# BpodMainBoard_r0_5_1.net
KiCad netlist of a schematic drawn in EAGLE
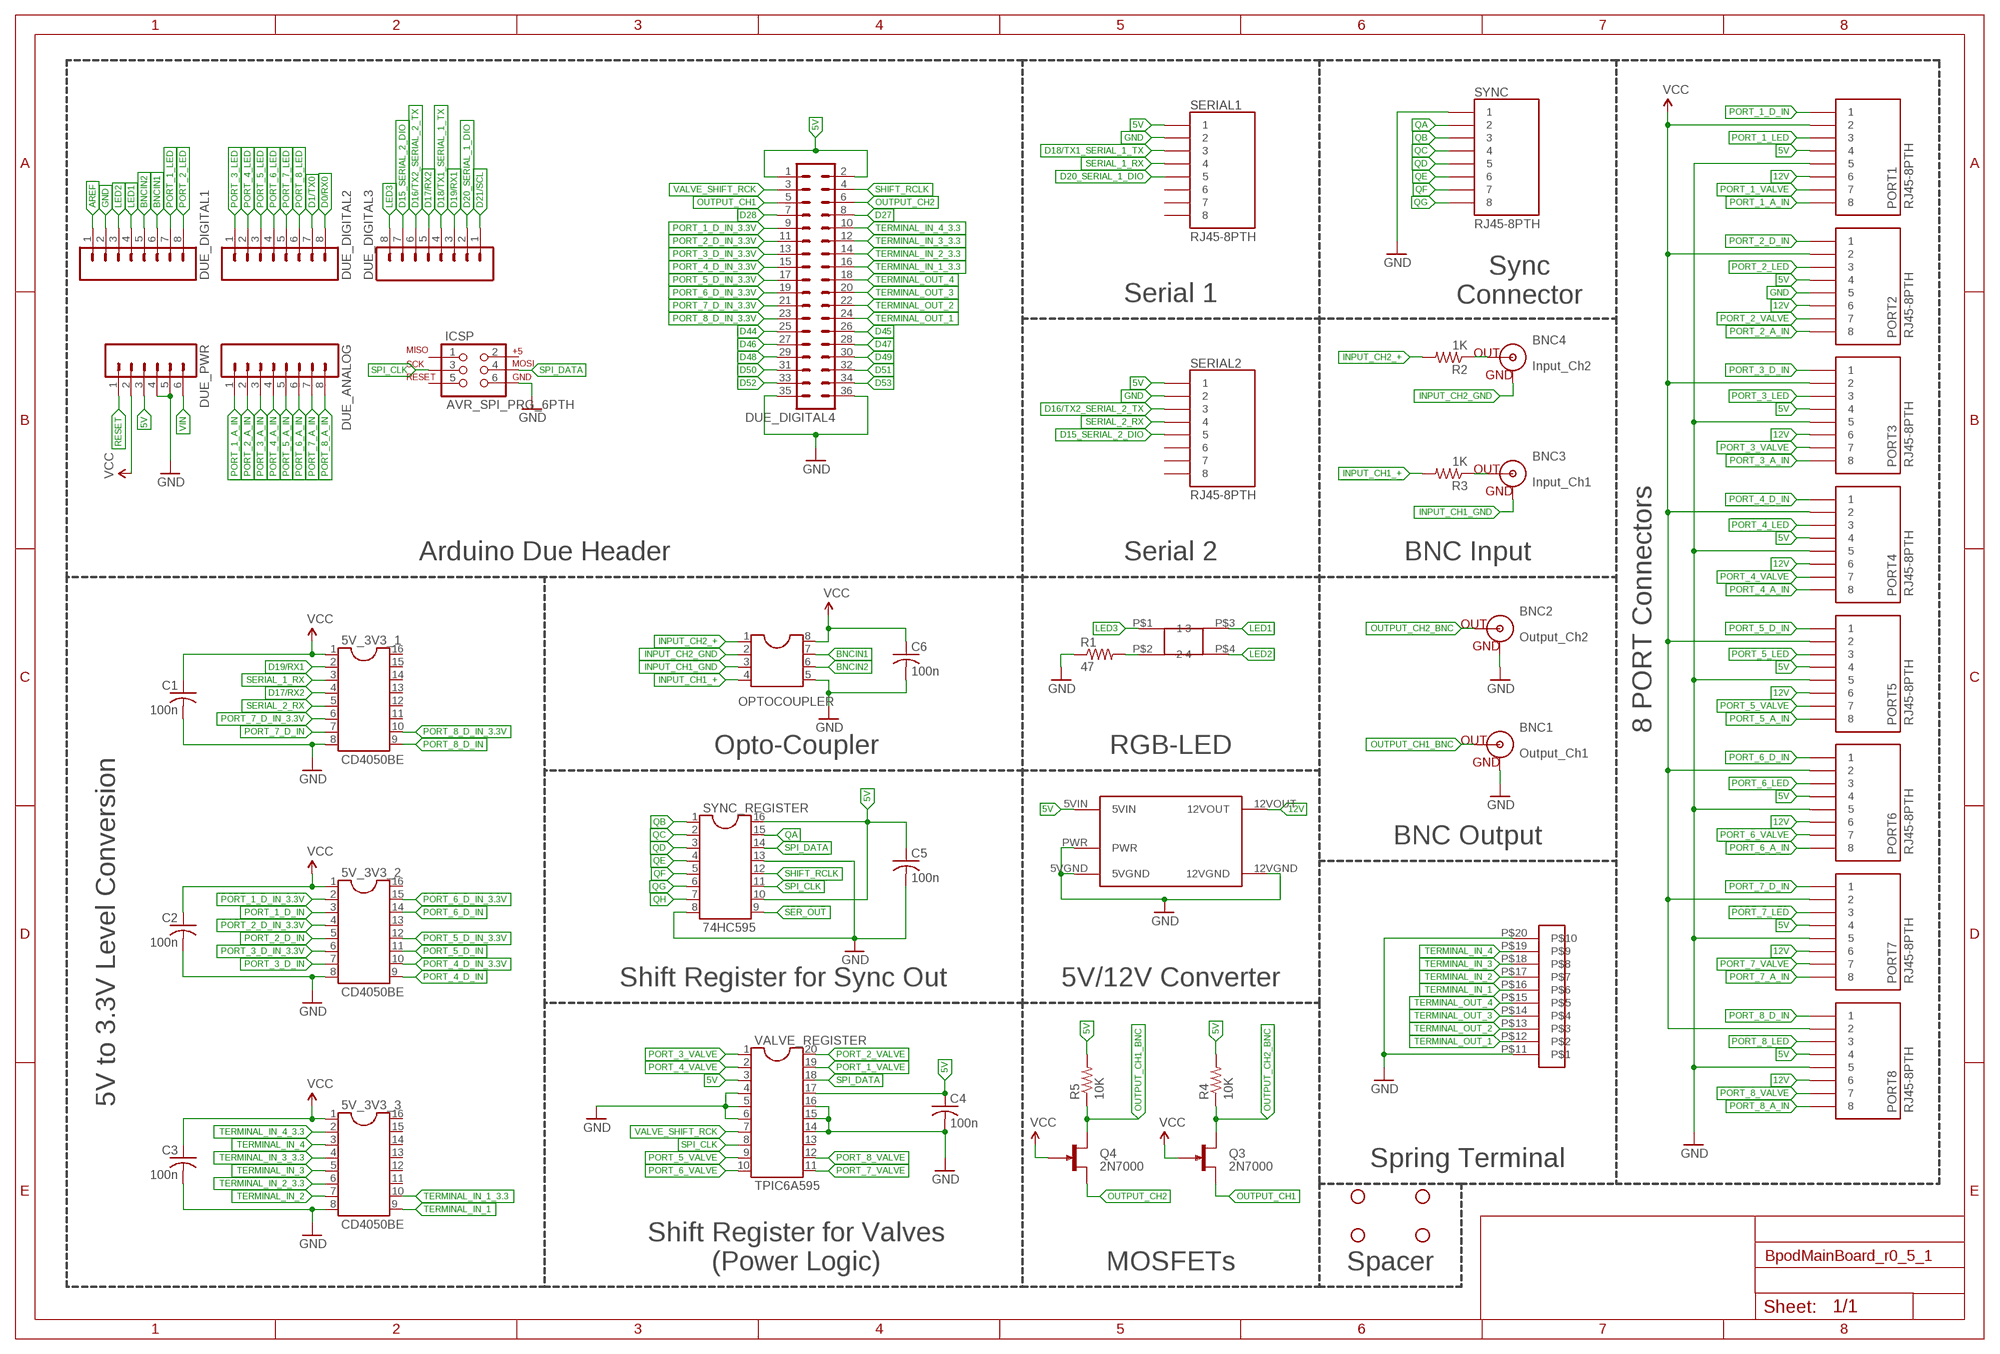
[diagram p0: schematic, sheet 1]

(export (version "E")
  (design (tool "Eeschema 10.0.6"))
  (components
    (comp (ref "5V_3V3_1")
      (value "CD4050BE")
      (footprint "eagle-import:DIL16")
      (libsource (lib "eagle-import") (part "DIL16"))
    )
    (comp (ref "5V_3V3_2")
      (value "CD4050BE")
      (footprint "eagle-import:DIL16")
      (libsource (lib "eagle-import") (part "DIL16"))
    )
    (comp (ref "5V_3V3_3")
      (value "CD4050BE")
      (footprint "eagle-import:DIL16")
      (libsource (lib "eagle-import") (part "DIL16"))
    )
    (comp (ref "BNC1")
      (value "Output_Ch1")
      (footprint "eagle-import:BNC")
      (libsource (lib "eagle-import") (part "BNCPTH"))
    )
    (comp (ref "BNC2")
      (value "Output_Ch2")
      (footprint "eagle-import:BNC")
      (libsource (lib "eagle-import") (part "BNCPTH"))
    )
    (comp (ref "BNC3")
      (value "Input_Ch1")
      (footprint "eagle-import:BNC")
      (libsource (lib "eagle-import") (part "BNCPTH"))
    )
    (comp (ref "BNC4")
      (value "Input_Ch2")
      (footprint "eagle-import:BNC")
      (libsource (lib "eagle-import") (part "BNCPTH"))
    )
    (comp (ref "C1")
      (value "100n")
      (footprint "eagle-import:C025-024X044")
      (libsource (lib "eagle-import") (part "C-US025-024X044"))
    )
    (comp (ref "C2")
      (value "100n")
      (footprint "eagle-import:C025-024X044")
      (libsource (lib "eagle-import") (part "C-US025-024X044"))
    )
    (comp (ref "C3")
      (value "100n")
      (footprint "eagle-import:C025-024X044")
      (libsource (lib "eagle-import") (part "C-US025-024X044"))
    )
    (comp (ref "C4")
      (value "100n")
      (footprint "eagle-import:C025-024X044")
      (libsource (lib "eagle-import") (part "C-US025-024X044"))
    )
    (comp (ref "C5")
      (value "100n")
      (footprint "eagle-import:C025-024X044")
      (libsource (lib "eagle-import") (part "C-US025-024X044"))
    )
    (comp (ref "C6")
      (value "100n")
      (footprint "eagle-import:C025-024X044")
      (libsource (lib "eagle-import") (part "C-US025-024X044"))
    )
    (comp (ref "DUE_ANALOG")
      (value "M081X08")
      (footprint "eagle-import:1X08")
      (libsource (lib "eagle-import") (part "M081X08"))
    )
    (comp (ref "DUE_DIGITAL1")
      (value "M081X08")
      (footprint "eagle-import:1X08")
      (libsource (lib "eagle-import") (part "M081X08"))
    )
    (comp (ref "DUE_DIGITAL2")
      (value "M081X08")
      (footprint "eagle-import:1X08")
      (libsource (lib "eagle-import") (part "M081X08"))
    )
    (comp (ref "DUE_DIGITAL3")
      (value "M081X08")
      (footprint "eagle-import:1X08")
      (libsource (lib "eagle-import") (part "M081X08"))
    )
    (comp (ref "DUE_DIGITAL4")
      (value "MA18-2")
      (footprint "eagle-import:MA18-2")
      (libsource (lib "eagle-import") (part "MA18-2"))
    )
    (comp (ref "DUE_PWR")
      (value "M06SIP")
      (footprint "eagle-import:1X06")
      (fields (field (name "SPICEPREFIX") "X"))
      (libsource (lib "eagle-import") (part "M06SIP"))
    )
    (comp (ref "ICSP")
      (value "AVR_SPI_PRG_6PTH")
      (footprint "eagle-import:2X3")
      (libsource (lib "eagle-import") (part "AVR_SPI_PRG_6PTH"))
    )
    (comp (ref "JP1")
      (value "STAND-OFF")
      (footprint "eagle-import:STAND-OFF")
      (libsource (lib "eagle-import") (part "STAND-OFF"))
    )
    (comp (ref "JP2")
      (value "STAND-OFF")
      (footprint "eagle-import:STAND-OFF")
      (libsource (lib "eagle-import") (part "STAND-OFF"))
    )
    (comp (ref "JP3")
      (value "STAND-OFF")
      (footprint "eagle-import:STAND-OFF")
      (libsource (lib "eagle-import") (part "STAND-OFF"))
    )
    (comp (ref "JP4")
      (value "STAND-OFF")
      (footprint "eagle-import:STAND-OFF")
      (libsource (lib "eagle-import") (part "STAND-OFF"))
    )
    (comp (ref "OPTOCOUPLER")
      (value "DIL8")
      (footprint "eagle-import:DIL08")
      (libsource (lib "eagle-import") (part "DIL8"))
    )
    (comp (ref "PORT1")
      (value "RJ45-8PTH")
      (footprint "eagle-import:RJ45-8")
      (libsource (lib "eagle-import") (part "RJ45-8PTH"))
    )
    (comp (ref "PORT2")
      (value "RJ45-8PTH")
      (footprint "eagle-import:RJ45-8")
      (libsource (lib "eagle-import") (part "RJ45-8PTH"))
    )
    (comp (ref "PORT3")
      (value "RJ45-8PTH")
      (footprint "eagle-import:RJ45-8")
      (libsource (lib "eagle-import") (part "RJ45-8PTH"))
    )
    (comp (ref "PORT4")
      (value "RJ45-8PTH")
      (footprint "eagle-import:RJ45-8")
      (libsource (lib "eagle-import") (part "RJ45-8PTH"))
    )
    (comp (ref "PORT5")
      (value "RJ45-8PTH")
      (footprint "eagle-import:RJ45-8")
      (libsource (lib "eagle-import") (part "RJ45-8PTH"))
    )
    (comp (ref "PORT6")
      (value "RJ45-8PTH")
      (footprint "eagle-import:RJ45-8")
      (libsource (lib "eagle-import") (part "RJ45-8PTH"))
    )
    (comp (ref "PORT7")
      (value "RJ45-8PTH")
      (footprint "eagle-import:RJ45-8")
      (libsource (lib "eagle-import") (part "RJ45-8PTH"))
    )
    (comp (ref "PORT8")
      (value "RJ45-8PTH")
      (footprint "eagle-import:RJ45-8")
      (libsource (lib "eagle-import") (part "RJ45-8PTH"))
    )
    (comp (ref "Q3")
      (value "2N7000")
      (footprint "eagle-import:TO92F")
      (libsource (lib "eagle-import") (part "2N3819"))
    )
    (comp (ref "Q4")
      (value "2N7000")
      (footprint "eagle-import:TO92F")
      (libsource (lib "eagle-import") (part "2N3819"))
    )
    (comp (ref "R1")
      (value "47")
      (footprint "eagle-import:0207_10")
      (libsource (lib "eagle-import") (part "R-US_0207/10"))
    )
    (comp (ref "R2")
      (value "1K")
      (footprint "eagle-import:0207_10")
      (libsource (lib "eagle-import") (part "R-US_0207/10"))
    )
    (comp (ref "R3")
      (value "1K")
      (footprint "eagle-import:0207_10")
      (libsource (lib "eagle-import") (part "R-US_0207/10"))
    )
    (comp (ref "R4")
      (value "10K")
      (footprint "eagle-import:0207_10")
      (libsource (lib "eagle-import") (part "R-US_0207/10"))
    )
    (comp (ref "R5")
      (value "10K")
      (footprint "eagle-import:0207_10")
      (libsource (lib "eagle-import") (part "R-US_0207/10"))
    )
    (comp (ref "SERIAL1")
      (value "RJ45-8PTH")
      (footprint "eagle-import:RJ45-8")
      (libsource (lib "eagle-import") (part "RJ45-8PTH"))
    )
    (comp (ref "SERIAL2")
      (value "RJ45-8PTH")
      (footprint "eagle-import:RJ45-8")
      (libsource (lib "eagle-import") (part "RJ45-8PTH"))
    )
    (comp (ref "SPRINGTERMINAL")
      (value "10POS_SPRING_TERMINAL")
      (footprint "eagle-import:10POS_SCREW_TERMINAL")
      (libsource (lib "eagle-import") (part "10POS_SPRING_TERMINAL"))
    )
    (comp (ref "SYNC")
      (value "RJ45-8PTH")
      (footprint "eagle-import:RJ45-8")
      (libsource (lib "eagle-import") (part "RJ45-8PTH"))
    )
    (comp (ref "SYNC_REGISTER")
      (value "74HC595")
      (footprint "eagle-import:DIL16")
      (libsource (lib "eagle-import") (part "DIL16"))
    )
    (comp (ref "U$5")
      (value "TDK_LAMBDA_5V_TO_12V")
      (footprint "eagle-import:TDK_LAMBDA_5V_12V")
      (libsource (lib "eagle-import") (part "TDK_LAMBDA_5V_TO_12V"))
    )
    (comp (ref "U$8")
      (value "SQUARE_TRICOLOR_LED")
      (footprint "eagle-import:SQUARE_TRICOLOR_LED")
      (libsource (lib "eagle-import") (part "SQUARE_TRICOLOR_LED"))
    )
    (comp (ref "VALVE_REGISTER")
      (value "TPIC6A595")
      (footprint "eagle-import:DIL20")
      (libsource (lib "eagle-import") (part "DIL20"))
    )
  )
  (nets
    (net (code "1") (name "5V") (class "Default")
      (node (ref "C4") (pin "1") (pinfunction "1_1") (pintype "passive"))
      (node (ref "C5") (pin "1") (pinfunction "1_1") (pintype "passive"))
      (node (ref "DUE_DIGITAL4") (pin "1") (pinfunction "1_1") (pintype "passive"))
      (node (ref "DUE_DIGITAL4") (pin "2") (pinfunction "2_2") (pintype "passive"))
      (node (ref "DUE_PWR") (pin "3") (pinfunction "3_3") (pintype "passive"))
      (node (ref "PORT1") (pin "4") (pinfunction "4_4") (pintype "bidirectional"))
      (node (ref "PORT2") (pin "4") (pinfunction "4_4") (pintype "bidirectional"))
      (node (ref "PORT3") (pin "4") (pinfunction "4_4") (pintype "bidirectional"))
      (node (ref "PORT4") (pin "4") (pinfunction "4_4") (pintype "bidirectional"))
      (node (ref "PORT5") (pin "4") (pinfunction "4_4") (pintype "bidirectional"))
      (node (ref "PORT6") (pin "4") (pinfunction "4_4") (pintype "bidirectional"))
      (node (ref "PORT7") (pin "4") (pinfunction "4_4") (pintype "bidirectional"))
      (node (ref "PORT8") (pin "4") (pinfunction "4_4") (pintype "bidirectional"))
      (node (ref "R4") (pin "2") (pinfunction "2_2") (pintype "passive"))
      (node (ref "R5") (pin "2") (pinfunction "2_2") (pintype "passive"))
      (node (ref "SERIAL1") (pin "1") (pinfunction "1_1") (pintype "bidirectional"))
      (node (ref "SERIAL2") (pin "1") (pinfunction "1_1") (pintype "bidirectional"))
      (node (ref "SYNC_REGISTER") (pin "10") (pinfunction "10_10") (pintype "passive"))
      (node (ref "SYNC_REGISTER") (pin "16") (pinfunction "16_16") (pintype "passive"))
      (node (ref "U$5") (pin "5VIN") (pinfunction "5VIN_5VIN") (pintype "bidirectional"))
      (node (ref "VALVE_REGISTER") (pin "17") (pinfunction "17_17") (pintype "passive"))
      (node (ref "VALVE_REGISTER") (pin "3") (pinfunction "3_3") (pintype "passive"))
    )
    (net (code "2") (name "12V") (class "Default")
      (node (ref "PORT1") (pin "6") (pinfunction "6_6") (pintype "bidirectional"))
      (node (ref "PORT2") (pin "6") (pinfunction "6_6") (pintype "bidirectional"))
      (node (ref "PORT3") (pin "6") (pinfunction "6_6") (pintype "bidirectional"))
      (node (ref "PORT4") (pin "6") (pinfunction "6_6") (pintype "bidirectional"))
      (node (ref "PORT5") (pin "6") (pinfunction "6_6") (pintype "bidirectional"))
      (node (ref "PORT6") (pin "6") (pinfunction "6_6") (pintype "bidirectional"))
      (node (ref "PORT7") (pin "6") (pinfunction "6_6") (pintype "bidirectional"))
      (node (ref "PORT8") (pin "6") (pinfunction "6_6") (pintype "bidirectional"))
      (node (ref "U$5") (pin "12VOUT") (pinfunction "12VOUT_12VOUT") (pintype "bidirectional"))
    )
    (net (code "3") (name "AREF") (class "Default")
      (node (ref "DUE_DIGITAL1") (pin "1") (pinfunction "1_1") (pintype "passive"))
    )
    (net (code "4") (name "BNCIN1") (class "Default")
      (node (ref "DUE_DIGITAL1") (pin "6") (pinfunction "6_6") (pintype "passive"))
      (node (ref "OPTOCOUPLER") (pin "7") (pinfunction "7_7") (pintype "passive"))
    )
    (net (code "5") (name "BNCIN2") (class "Default")
      (node (ref "DUE_DIGITAL1") (pin "5") (pinfunction "5_5") (pintype "passive"))
      (node (ref "OPTOCOUPLER") (pin "6") (pinfunction "6_6") (pintype "passive"))
    )
    (net (code "6") (name "D0{slash}RX0") (class "Default")
      (node (ref "DUE_DIGITAL2") (pin "8") (pinfunction "8_8") (pintype "passive"))
    )
    (net (code "7") (name "D1{slash}TX0") (class "Default")
      (node (ref "DUE_DIGITAL2") (pin "7") (pinfunction "7_7") (pintype "passive"))
    )
    (net (code "8") (name "D15_SERIAL_2_DIO") (class "Default")
      (node (ref "DUE_DIGITAL3") (pin "7") (pinfunction "7_7") (pintype "passive"))
      (node (ref "SERIAL2") (pin "5") (pinfunction "5_5") (pintype "bidirectional"))
    )
    (net (code "9") (name "D16{slash}TX2_SERIAL_2_TX") (class "Default")
      (node (ref "DUE_DIGITAL3") (pin "6") (pinfunction "6_6") (pintype "passive"))
      (node (ref "SERIAL2") (pin "3") (pinfunction "3_3") (pintype "bidirectional"))
    )
    (net (code "10") (name "D17{slash}RX2") (class "Default")
      (node (ref "5V_3V3_1") (pin "4") (pinfunction "4_4") (pintype "passive"))
      (node (ref "DUE_DIGITAL3") (pin "5") (pinfunction "5_5") (pintype "passive"))
    )
    (net (code "11") (name "D18{slash}TX1_SERIAL_1_TX") (class "Default")
      (node (ref "DUE_DIGITAL3") (pin "4") (pinfunction "4_4") (pintype "passive"))
      (node (ref "SERIAL1") (pin "3") (pinfunction "3_3") (pintype "bidirectional"))
    )
    (net (code "12") (name "D19{slash}RX1") (class "Default")
      (node (ref "5V_3V3_1") (pin "2") (pinfunction "2_2") (pintype "passive"))
      (node (ref "DUE_DIGITAL3") (pin "3") (pinfunction "3_3") (pintype "passive"))
    )
    (net (code "13") (name "D20_SERIAL_1_DIO") (class "Default")
      (node (ref "DUE_DIGITAL3") (pin "2") (pinfunction "2_2") (pintype "passive"))
      (node (ref "SERIAL1") (pin "5") (pinfunction "5_5") (pintype "bidirectional"))
    )
    (net (code "14") (name "D21{slash}SCL") (class "Default")
      (node (ref "DUE_DIGITAL3") (pin "1") (pinfunction "1_1") (pintype "passive"))
    )
    (net (code "15") (name "D27") (class "Default")
      (node (ref "DUE_DIGITAL4") (pin "8") (pinfunction "8_8") (pintype "passive"))
    )
    (net (code "16") (name "D28") (class "Default")
      (node (ref "DUE_DIGITAL4") (pin "7") (pinfunction "7_7") (pintype "passive"))
    )
    (net (code "17") (name "D44") (class "Default")
      (node (ref "DUE_DIGITAL4") (pin "25") (pinfunction "25_25") (pintype "passive"))
    )
    (net (code "18") (name "D45") (class "Default")
      (node (ref "DUE_DIGITAL4") (pin "26") (pinfunction "26_26") (pintype "passive"))
    )
    (net (code "19") (name "D46") (class "Default")
      (node (ref "DUE_DIGITAL4") (pin "27") (pinfunction "27_27") (pintype "passive"))
    )
    (net (code "20") (name "D47") (class "Default")
      (node (ref "DUE_DIGITAL4") (pin "28") (pinfunction "28_28") (pintype "passive"))
    )
    (net (code "21") (name "D48") (class "Default")
      (node (ref "DUE_DIGITAL4") (pin "29") (pinfunction "29_29") (pintype "passive"))
    )
    (net (code "22") (name "D49") (class "Default")
      (node (ref "DUE_DIGITAL4") (pin "30") (pinfunction "30_30") (pintype "passive"))
    )
    (net (code "23") (name "D50") (class "Default")
      (node (ref "DUE_DIGITAL4") (pin "31") (pinfunction "31_31") (pintype "passive"))
    )
    (net (code "24") (name "D51") (class "Default")
      (node (ref "DUE_DIGITAL4") (pin "32") (pinfunction "32_32") (pintype "passive"))
    )
    (net (code "25") (name "D52") (class "Default")
      (node (ref "DUE_DIGITAL4") (pin "33") (pinfunction "33_33") (pintype "passive"))
    )
    (net (code "26") (name "D53") (class "Default")
      (node (ref "DUE_DIGITAL4") (pin "34") (pinfunction "34_34") (pintype "passive"))
    )
    (net (code "27") (name "GND") (class "Default")
      (node (ref "5V_3V3_1") (pin "8") (pinfunction "8_8") (pintype "passive"))
      (node (ref "5V_3V3_2") (pin "8") (pinfunction "8_8") (pintype "passive"))
      (node (ref "5V_3V3_3") (pin "8") (pinfunction "8_8") (pintype "passive"))
      (node (ref "BNC1") (pin "GND") (pinfunction "GND_GND") (pintype "bidirectional"))
      (node (ref "BNC2") (pin "GND") (pinfunction "GND_GND") (pintype "bidirectional"))
      (node (ref "C1") (pin "2") (pinfunction "2_2") (pintype "passive"))
      (node (ref "C2") (pin "2") (pinfunction "2_2") (pintype "passive"))
      (node (ref "C3") (pin "2") (pinfunction "2_2") (pintype "passive"))
      (node (ref "C4") (pin "2") (pinfunction "2_2") (pintype "passive"))
      (node (ref "C5") (pin "2") (pinfunction "2_2") (pintype "passive"))
      (node (ref "C6") (pin "2") (pinfunction "2_2") (pintype "passive"))
      (node (ref "DUE_DIGITAL1") (pin "2") (pinfunction "2_2") (pintype "passive"))
      (node (ref "DUE_DIGITAL4") (pin "35") (pinfunction "35_35") (pintype "passive"))
      (node (ref "DUE_DIGITAL4") (pin "36") (pinfunction "36_36") (pintype "passive"))
      (node (ref "DUE_PWR") (pin "4") (pinfunction "4_4") (pintype "passive"))
      (node (ref "DUE_PWR") (pin "5") (pinfunction "5_5") (pintype "passive"))
      (node (ref "ICSP") (pin "6") (pinfunction "6_6") (pintype "passive"))
      (node (ref "OPTOCOUPLER") (pin "5") (pinfunction "5_5") (pintype "passive"))
      (node (ref "PORT1") (pin "5") (pinfunction "5_5") (pintype "bidirectional"))
      (node (ref "PORT2") (pin "5") (pinfunction "5_5") (pintype "bidirectional"))
      (node (ref "PORT3") (pin "5") (pinfunction "5_5") (pintype "bidirectional"))
      (node (ref "PORT4") (pin "5") (pinfunction "5_5") (pintype "bidirectional"))
      (node (ref "PORT5") (pin "5") (pinfunction "5_5") (pintype "bidirectional"))
      (node (ref "PORT6") (pin "5") (pinfunction "5_5") (pintype "bidirectional"))
      (node (ref "PORT7") (pin "5") (pinfunction "5_5") (pintype "bidirectional"))
      (node (ref "PORT8") (pin "5") (pinfunction "5_5") (pintype "bidirectional"))
      (node (ref "R1") (pin "1") (pinfunction "1_1") (pintype "passive"))
      (node (ref "SERIAL1") (pin "2") (pinfunction "2_2") (pintype "bidirectional"))
      (node (ref "SERIAL2") (pin "2") (pinfunction "2_2") (pintype "bidirectional"))
      (node (ref "SPRINGTERMINAL") (pin "P$11") (pinfunction "P$1_P$11") (pintype "bidirectional"))
      (node (ref "SPRINGTERMINAL") (pin "P$20") (pinfunction "P$10_P$20") (pintype "bidirectional"))
      (node (ref "SYNC") (pin "1") (pinfunction "1_1") (pintype "bidirectional"))
      (node (ref "SYNC_REGISTER") (pin "13") (pinfunction "13_13") (pintype "passive"))
      (node (ref "SYNC_REGISTER") (pin "8") (pinfunction "8_8") (pintype "passive"))
      (node (ref "U$5") (pin "12VGND") (pinfunction "12VGND_12VGND") (pintype "bidirectional"))
      (node (ref "U$5") (pin "5VGND") (pinfunction "5VGND_5VGND") (pintype "bidirectional"))
      (node (ref "U$5") (pin "PWR") (pinfunction "PWR_PWR") (pintype "bidirectional"))
      (node (ref "VALVE_REGISTER") (pin "14") (pinfunction "14_14") (pintype "passive"))
      (node (ref "VALVE_REGISTER") (pin "15") (pinfunction "15_15") (pintype "passive"))
      (node (ref "VALVE_REGISTER") (pin "16") (pinfunction "16_16") (pintype "passive"))
      (node (ref "VALVE_REGISTER") (pin "4") (pinfunction "4_4") (pintype "passive"))
      (node (ref "VALVE_REGISTER") (pin "5") (pinfunction "5_5") (pintype "passive"))
      (node (ref "VALVE_REGISTER") (pin "6") (pinfunction "6_6") (pintype "passive"))
    )
    (net (code "28") (name "INPUT_CH1_+") (class "Default")
      (node (ref "OPTOCOUPLER") (pin "4") (pinfunction "4_4") (pintype "passive"))
      (node (ref "R3") (pin "2") (pinfunction "2_2") (pintype "passive"))
    )
    (net (code "29") (name "INPUT_CH1_GND") (class "Default")
      (node (ref "BNC3") (pin "GND") (pinfunction "GND_GND") (pintype "bidirectional"))
      (node (ref "OPTOCOUPLER") (pin "3") (pinfunction "3_3") (pintype "passive"))
    )
    (net (code "30") (name "INPUT_CH2_+") (class "Default")
      (node (ref "OPTOCOUPLER") (pin "1") (pinfunction "1_1") (pintype "passive"))
      (node (ref "R2") (pin "2") (pinfunction "2_2") (pintype "passive"))
    )
    (net (code "31") (name "INPUT_CH2_GND") (class "Default")
      (node (ref "BNC4") (pin "GND") (pinfunction "GND_GND") (pintype "bidirectional"))
      (node (ref "OPTOCOUPLER") (pin "2") (pinfunction "2_2") (pintype "passive"))
    )
    (net (code "32") (name "LED1") (class "Default")
      (node (ref "DUE_DIGITAL1") (pin "4") (pinfunction "4_4") (pintype "passive"))
      (node (ref "U$8") (pin "P$3") (pinfunction "3_P$3") (pintype "bidirectional"))
    )
    (net (code "33") (name "LED2") (class "Default")
      (node (ref "DUE_DIGITAL1") (pin "3") (pinfunction "3_3") (pintype "passive"))
      (node (ref "U$8") (pin "P$4") (pinfunction "4_P$4") (pintype "bidirectional"))
    )
    (net (code "34") (name "LED3") (class "Default")
      (node (ref "DUE_DIGITAL3") (pin "8") (pinfunction "8_8") (pintype "passive"))
      (node (ref "U$8") (pin "P$1") (pinfunction "1_P$1") (pintype "bidirectional"))
    )
    (net (code "35") (name "Net-(BNC3-OUT)") (class "Default")
      (node (ref "BNC3") (pin "S") (pinfunction "OUT_S") (pintype "bidirectional"))
      (node (ref "R3") (pin "1") (pinfunction "1_1") (pintype "passive"))
    )
    (net (code "36") (name "Net-(BNC4-OUT)") (class "Default")
      (node (ref "BNC4") (pin "S") (pinfunction "OUT_S") (pintype "bidirectional"))
      (node (ref "R2") (pin "1") (pinfunction "1_1") (pintype "passive"))
    )
    (net (code "37") (name "Net-(U$8-2)") (class "Default")
      (node (ref "R1") (pin "2") (pinfunction "2_2") (pintype "passive"))
      (node (ref "U$8") (pin "P$2") (pinfunction "2_P$2") (pintype "bidirectional"))
    )
    (net (code "38") (name "OUTPUT_CH1") (class "Default")
      (node (ref "DUE_DIGITAL4") (pin "5") (pinfunction "5_5") (pintype "passive"))
      (node (ref "Q3") (pin "S") (pinfunction "S_S") (pintype "passive"))
    )
    (net (code "39") (name "OUTPUT_CH1_BNC") (class "Default")
      (node (ref "BNC1") (pin "S") (pinfunction "OUT_S") (pintype "bidirectional"))
      (node (ref "Q4") (pin "D") (pinfunction "D_D") (pintype "passive"))
      (node (ref "R5") (pin "1") (pinfunction "1_1") (pintype "passive"))
    )
    (net (code "40") (name "OUTPUT_CH2") (class "Default")
      (node (ref "DUE_DIGITAL4") (pin "6") (pinfunction "6_6") (pintype "passive"))
      (node (ref "Q4") (pin "S") (pinfunction "S_S") (pintype "passive"))
    )
    (net (code "41") (name "OUTPUT_CH2_BNC") (class "Default")
      (node (ref "BNC2") (pin "S") (pinfunction "OUT_S") (pintype "bidirectional"))
      (node (ref "Q3") (pin "D") (pinfunction "D_D") (pintype "passive"))
      (node (ref "R4") (pin "1") (pinfunction "1_1") (pintype "passive"))
    )
    (net (code "42") (name "PORT_1_A_IN") (class "Default")
      (node (ref "DUE_ANALOG") (pin "1") (pinfunction "1_1") (pintype "passive"))
      (node (ref "PORT1") (pin "8") (pinfunction "8_8") (pintype "bidirectional"))
    )
    (net (code "43") (name "PORT_1_D_IN") (class "Default")
      (node (ref "5V_3V3_2") (pin "3") (pinfunction "3_3") (pintype "passive"))
      (node (ref "PORT1") (pin "1") (pinfunction "1_1") (pintype "bidirectional"))
    )
    (net (code "44") (name "PORT_1_D_IN_3.3V") (class "Default")
      (node (ref "5V_3V3_2") (pin "2") (pinfunction "2_2") (pintype "passive"))
      (node (ref "DUE_DIGITAL4") (pin "9") (pinfunction "9_9") (pintype "passive"))
    )
    (net (code "45") (name "PORT_1_LED") (class "Default")
      (node (ref "DUE_DIGITAL1") (pin "7") (pinfunction "7_7") (pintype "passive"))
      (node (ref "PORT1") (pin "3") (pinfunction "3_3") (pintype "bidirectional"))
    )
    (net (code "46") (name "PORT_1_VALVE") (class "Default")
      (node (ref "PORT1") (pin "7") (pinfunction "7_7") (pintype "bidirectional"))
      (node (ref "VALVE_REGISTER") (pin "19") (pinfunction "19_19") (pintype "passive"))
    )
    (net (code "47") (name "PORT_2_A_IN") (class "Default")
      (node (ref "DUE_ANALOG") (pin "2") (pinfunction "2_2") (pintype "passive"))
      (node (ref "PORT2") (pin "8") (pinfunction "8_8") (pintype "bidirectional"))
    )
    (net (code "48") (name "PORT_2_D_IN") (class "Default")
      (node (ref "5V_3V3_2") (pin "5") (pinfunction "5_5") (pintype "passive"))
      (node (ref "PORT2") (pin "1") (pinfunction "1_1") (pintype "bidirectional"))
    )
    (net (code "49") (name "PORT_2_D_IN_3.3V") (class "Default")
      (node (ref "5V_3V3_2") (pin "4") (pinfunction "4_4") (pintype "passive"))
      (node (ref "DUE_DIGITAL4") (pin "11") (pinfunction "11_11") (pintype "passive"))
    )
    (net (code "50") (name "PORT_2_LED") (class "Default")
      (node (ref "DUE_DIGITAL1") (pin "8") (pinfunction "8_8") (pintype "passive"))
      (node (ref "PORT2") (pin "3") (pinfunction "3_3") (pintype "bidirectional"))
    )
    (net (code "51") (name "PORT_2_VALVE") (class "Default")
      (node (ref "PORT2") (pin "7") (pinfunction "7_7") (pintype "bidirectional"))
      (node (ref "VALVE_REGISTER") (pin "20") (pinfunction "20_20") (pintype "passive"))
    )
    (net (code "52") (name "PORT_3_A_IN") (class "Default")
      (node (ref "DUE_ANALOG") (pin "3") (pinfunction "3_3") (pintype "passive"))
      (node (ref "PORT3") (pin "8") (pinfunction "8_8") (pintype "bidirectional"))
    )
    (net (code "53") (name "PORT_3_D_IN") (class "Default")
      (node (ref "5V_3V3_2") (pin "7") (pinfunction "7_7") (pintype "passive"))
      (node (ref "PORT3") (pin "1") (pinfunction "1_1") (pintype "bidirectional"))
    )
    (net (code "54") (name "PORT_3_D_IN_3.3V") (class "Default")
      (node (ref "5V_3V3_2") (pin "6") (pinfunction "6_6") (pintype "passive"))
      (node (ref "DUE_DIGITAL4") (pin "13") (pinfunction "13_13") (pintype "passive"))
    )
    (net (code "55") (name "PORT_3_LED") (class "Default")
      (node (ref "DUE_DIGITAL2") (pin "1") (pinfunction "1_1") (pintype "passive"))
      (node (ref "PORT3") (pin "3") (pinfunction "3_3") (pintype "bidirectional"))
    )
    (net (code "56") (name "PORT_3_VALVE") (class "Default")
      (node (ref "PORT3") (pin "7") (pinfunction "7_7") (pintype "bidirectional"))
      (node (ref "VALVE_REGISTER") (pin "1") (pinfunction "1_1") (pintype "passive"))
    )
    (net (code "57") (name "PORT_4_A_IN") (class "Default")
      (node (ref "DUE_ANALOG") (pin "4") (pinfunction "4_4") (pintype "passive"))
      (node (ref "PORT4") (pin "8") (pinfunction "8_8") (pintype "bidirectional"))
    )
    (net (code "58") (name "PORT_4_D_IN") (class "Default")
      (node (ref "5V_3V3_2") (pin "9") (pinfunction "9_9") (pintype "passive"))
      (node (ref "PORT4") (pin "1") (pinfunction "1_1") (pintype "bidirectional"))
    )
    (net (code "59") (name "PORT_4_D_IN_3.3V") (class "Default")
      (node (ref "5V_3V3_2") (pin "10") (pinfunction "10_10") (pintype "passive"))
      (node (ref "DUE_DIGITAL4") (pin "15") (pinfunction "15_15") (pintype "passive"))
    )
    (net (code "60") (name "PORT_4_LED") (class "Default")
      (node (ref "DUE_DIGITAL2") (pin "2") (pinfunction "2_2") (pintype "passive"))
      (node (ref "PORT4") (pin "3") (pinfunction "3_3") (pintype "bidirectional"))
    )
    (net (code "61") (name "PORT_4_VALVE") (class "Default")
      (node (ref "PORT4") (pin "7") (pinfunction "7_7") (pintype "bidirectional"))
      (node (ref "VALVE_REGISTER") (pin "2") (pinfunction "2_2") (pintype "passive"))
    )
    (net (code "62") (name "PORT_5_A_IN") (class "Default")
      (node (ref "DUE_ANALOG") (pin "5") (pinfunction "5_5") (pintype "passive"))
      (node (ref "PORT5") (pin "8") (pinfunction "8_8") (pintype "bidirectional"))
    )
    (net (code "63") (name "PORT_5_D_IN") (class "Default")
      (node (ref "5V_3V3_2") (pin "11") (pinfunction "11_11") (pintype "passive"))
      (node (ref "PORT5") (pin "1") (pinfunction "1_1") (pintype "bidirectional"))
    )
    (net (code "64") (name "PORT_5_D_IN_3.3V") (class "Default")
      (node (ref "5V_3V3_2") (pin "12") (pinfunction "12_12") (pintype "passive"))
      (node (ref "DUE_DIGITAL4") (pin "17") (pinfunction "17_17") (pintype "passive"))
    )
    (net (code "65") (name "PORT_5_LED") (class "Default")
      (node (ref "DUE_DIGITAL2") (pin "3") (pinfunction "3_3") (pintype "passive"))
      (node (ref "PORT5") (pin "3") (pinfunction "3_3") (pintype "bidirectional"))
    )
    (net (code "66") (name "PORT_5_VALVE") (class "Default")
      (node (ref "PORT5") (pin "7") (pinfunction "7_7") (pintype "bidirectional"))
      (node (ref "VALVE_REGISTER") (pin "9") (pinfunction "9_9") (pintype "passive"))
    )
    (net (code "67") (name "PORT_6_A_IN") (class "Default")
      (node (ref "DUE_ANALOG") (pin "6") (pinfunction "6_6") (pintype "passive"))
      (node (ref "PORT6") (pin "8") (pinfunction "8_8") (pintype "bidirectional"))
    )
    (net (code "68") (name "PORT_6_D_IN") (class "Default")
      (node (ref "5V_3V3_2") (pin "14") (pinfunction "14_14") (pintype "passive"))
      (node (ref "PORT6") (pin "1") (pinfunction "1_1") (pintype "bidirectional"))
    )
    (net (code "69") (name "PORT_6_D_IN_3.3V") (class "Default")
      (node (ref "5V_3V3_2") (pin "15") (pinfunction "15_15") (pintype "passive"))
      (node (ref "DUE_DIGITAL4") (pin "19") (pinfunction "19_19") (pintype "passive"))
    )
    (net (code "70") (name "PORT_6_LED") (class "Default")
      (node (ref "DUE_DIGITAL2") (pin "4") (pinfunction "4_4") (pintype "passive"))
      (node (ref "PORT6") (pin "3") (pinfunction "3_3") (pintype "bidirectional"))
    )
    (net (code "71") (name "PORT_6_VALVE") (class "Default")
      (node (ref "PORT6") (pin "7") (pinfunction "7_7") (pintype "bidirectional"))
      (node (ref "VALVE_REGISTER") (pin "10") (pinfunction "10_10") (pintype "passive"))
    )
    (net (code "72") (name "PORT_7_A_IN") (class "Default")
      (node (ref "DUE_ANALOG") (pin "7") (pinfunction "7_7") (pintype "passive"))
      (node (ref "PORT7") (pin "8") (pinfunction "8_8") (pintype "bidirectional"))
    )
    (net (code "73") (name "PORT_7_D_IN") (class "Default")
      (node (ref "5V_3V3_1") (pin "7") (pinfunction "7_7") (pintype "passive"))
      (node (ref "PORT7") (pin "1") (pinfunction "1_1") (pintype "bidirectional"))
    )
    (net (code "74") (name "PORT_7_D_IN_3.3V") (class "Default")
      (node (ref "5V_3V3_1") (pin "6") (pinfunction "6_6") (pintype "passive"))
      (node (ref "DUE_DIGITAL4") (pin "21") (pinfunction "21_21") (pintype "passive"))
    )
    (net (code "75") (name "PORT_7_LED") (class "Default")
      (node (ref "DUE_DIGITAL2") (pin "5") (pinfunction "5_5") (pintype "passive"))
      (node (ref "PORT7") (pin "3") (pinfunction "3_3") (pintype "bidirectional"))
    )
    (net (code "76") (name "PORT_7_VALVE") (class "Default")
      (node (ref "PORT7") (pin "7") (pinfunction "7_7") (pintype "bidirectional"))
      (node (ref "VALVE_REGISTER") (pin "11") (pinfunction "11_11") (pintype "passive"))
    )
    (net (code "77") (name "PORT_8_A_IN") (class "Default")
      (node (ref "DUE_ANALOG") (pin "8") (pinfunction "8_8") (pintype "passive"))
      (node (ref "PORT8") (pin "8") (pinfunction "8_8") (pintype "bidirectional"))
    )
    (net (code "78") (name "PORT_8_D_IN") (class "Default")
      (node (ref "5V_3V3_1") (pin "9") (pinfunction "9_9") (pintype "passive"))
      (node (ref "PORT8") (pin "1") (pinfunction "1_1") (pintype "bidirectional"))
    )
    (net (code "79") (name "PORT_8_D_IN_3.3V") (class "Default")
      (node (ref "5V_3V3_1") (pin "10") (pinfunction "10_10") (pintype "passive"))
      (node (ref "DUE_DIGITAL4") (pin "23") (pinfunction "23_23") (pintype "passive"))
    )
    (net (code "80") (name "PORT_8_LED") (class "Default")
      (node (ref "DUE_DIGITAL2") (pin "6") (pinfunction "6_6") (pintype "passive"))
      (node (ref "PORT8") (pin "3") (pinfunction "3_3") (pintype "bidirectional"))
    )
    (net (code "81") (name "PORT_8_VALVE") (class "Default")
      (node (ref "PORT8") (pin "7") (pinfunction "7_7") (pintype "bidirectional"))
      (node (ref "VALVE_REGISTER") (pin "12") (pinfunction "12_12") (pintype "passive"))
    )
    (net (code "82") (name "QA") (class "Default")
      (node (ref "SYNC") (pin "2") (pinfunction "2_2") (pintype "bidirectional"))
      (node (ref "SYNC_REGISTER") (pin "15") (pinfunction "15_15") (pintype "passive"))
    )
    (net (code "83") (name "QB") (class "Default")
      (node (ref "SYNC") (pin "3") (pinfunction "3_3") (pintype "bidirectional"))
      (node (ref "SYNC_REGISTER") (pin "1") (pinfunction "1_1") (pintype "passive"))
    )
    (net (code "84") (name "QC") (class "Default")
      (node (ref "SYNC") (pin "4") (pinfunction "4_4") (pintype "bidirectional"))
      (node (ref "SYNC_REGISTER") (pin "2") (pinfunction "2_2") (pintype "passive"))
    )
    (net (code "85") (name "QD") (class "Default")
      (node (ref "SYNC") (pin "5") (pinfunction "5_5") (pintype "bidirectional"))
      (node (ref "SYNC_REGISTER") (pin "3") (pinfunction "3_3") (pintype "passive"))
    )
    (net (code "86") (name "QE") (class "Default")
      (node (ref "SYNC") (pin "6") (pinfunction "6_6") (pintype "bidirectional"))
      (node (ref "SYNC_REGISTER") (pin "4") (pinfunction "4_4") (pintype "passive"))
    )
    (net (code "87") (name "QF") (class "Default")
      (node (ref "SYNC") (pin "7") (pinfunction "7_7") (pintype "bidirectional"))
      (node (ref "SYNC_REGISTER") (pin "5") (pinfunction "5_5") (pintype "passive"))
    )
    (net (code "88") (name "QG") (class "Default")
      (node (ref "SYNC") (pin "8") (pinfunction "8_8") (pintype "bidirectional"))
      (node (ref "SYNC_REGISTER") (pin "6") (pinfunction "6_6") (pintype "passive"))
    )
    (net (code "89") (name "QH") (class "Default")
      (node (ref "SYNC_REGISTER") (pin "7") (pinfunction "7_7") (pintype "passive"))
    )
    (net (code "90") (name "RESET") (class "Default")
      (node (ref "DUE_PWR") (pin "1") (pinfunction "1_1") (pintype "passive"))
    )
    (net (code "91") (name "SERIAL_1_RX") (class "Default")
      (node (ref "5V_3V3_1") (pin "3") (pinfunction "3_3") (pintype "passive"))
      (node (ref "SERIAL1") (pin "4") (pinfunction "4_4") (pintype "bidirectional"))
    )
    (net (code "92") (name "SERIAL_2_RX") (class "Default")
      (node (ref "5V_3V3_1") (pin "5") (pinfunction "5_5") (pintype "passive"))
      (node (ref "SERIAL2") (pin "4") (pinfunction "4_4") (pintype "bidirectional"))
    )
    (net (code "93") (name "SER_OUT") (class "Default")
      (node (ref "SYNC_REGISTER") (pin "9") (pinfunction "9_9") (pintype "passive"))
    )
    (net (code "94") (name "SHIFT_RCLK") (class "Default")
      (node (ref "DUE_DIGITAL4") (pin "4") (pinfunction "4_4") (pintype "passive"))
      (node (ref "SYNC_REGISTER") (pin "12") (pinfunction "12_12") (pintype "passive"))
    )
    (net (code "95") (name "SPI_CLK") (class "Default")
      (node (ref "ICSP") (pin "3") (pinfunction "3_3") (pintype "passive"))
      (node (ref "SYNC_REGISTER") (pin "11") (pinfunction "11_11") (pintype "passive"))
      (node (ref "VALVE_REGISTER") (pin "8") (pinfunction "8_8") (pintype "passive"))
    )
    (net (code "96") (name "SPI_DATA") (class "Default")
      (node (ref "ICSP") (pin "4") (pinfunction "4_4") (pintype "passive"))
      (node (ref "SYNC_REGISTER") (pin "14") (pinfunction "14_14") (pintype "passive"))
      (node (ref "VALVE_REGISTER") (pin "18") (pinfunction "18_18") (pintype "passive"))
    )
    (net (code "97") (name "TERMINAL_IN_1") (class "Default")
      (node (ref "5V_3V3_3") (pin "9") (pinfunction "9_9") (pintype "passive"))
      (node (ref "SPRINGTERMINAL") (pin "P$16") (pinfunction "P$6_P$16") (pintype "bidirectional"))
    )
    (net (code "98") (name "TERMINAL_IN_1_3.3") (class "Default")
      (node (ref "5V_3V3_3") (pin "10") (pinfunction "10_10") (pintype "passive"))
      (node (ref "DUE_DIGITAL4") (pin "16") (pinfunction "16_16") (pintype "passive"))
    )
    (net (code "99") (name "TERMINAL_IN_2") (class "Default")
      (node (ref "5V_3V3_3") (pin "7") (pinfunction "7_7") (pintype "passive"))
      (node (ref "SPRINGTERMINAL") (pin "P$17") (pinfunction "P$7_P$17") (pintype "bidirectional"))
    )
    (net (code "100") (name "TERMINAL_IN_2_3.3") (class "Default")
      (node (ref "5V_3V3_3") (pin "6") (pinfunction "6_6") (pintype "passive"))
      (node (ref "DUE_DIGITAL4") (pin "14") (pinfunction "14_14") (pintype "passive"))
    )
    (net (code "101") (name "TERMINAL_IN_3") (class "Default")
      (node (ref "5V_3V3_3") (pin "5") (pinfunction "5_5") (pintype "passive"))
      (node (ref "SPRINGTERMINAL") (pin "P$18") (pinfunction "P$8_P$18") (pintype "bidirectional"))
    )
    (net (code "102") (name "TERMINAL_IN_3_3.3") (class "Default")
      (node (ref "5V_3V3_3") (pin "4") (pinfunction "4_4") (pintype "passive"))
      (node (ref "DUE_DIGITAL4") (pin "12") (pinfunction "12_12") (pintype "passive"))
    )
    (net (code "103") (name "TERMINAL_IN_4") (class "Default")
      (node (ref "5V_3V3_3") (pin "3") (pinfunction "3_3") (pintype "passive"))
      (node (ref "SPRINGTERMINAL") (pin "P$19") (pinfunction "P$9_P$19") (pintype "bidirectional"))
    )
    (net (code "104") (name "TERMINAL_IN_4_3.3") (class "Default")
      (node (ref "5V_3V3_3") (pin "2") (pinfunction "2_2") (pintype "passive"))
      (node (ref "DUE_DIGITAL4") (pin "10") (pinfunction "10_10") (pintype "passive"))
    )
    (net (code "105") (name "TERMINAL_OUT_1") (class "Default")
      (node (ref "DUE_DIGITAL4") (pin "24") (pinfunction "24_24") (pintype "passive"))
      (node (ref "SPRINGTERMINAL") (pin "P$12") (pinfunction "P$2_P$12") (pintype "bidirectional"))
    )
    (net (code "106") (name "TERMINAL_OUT_2") (class "Default")
      (node (ref "DUE_DIGITAL4") (pin "22") (pinfunction "22_22") (pintype "passive"))
      (node (ref "SPRINGTERMINAL") (pin "P$13") (pinfunction "P$3_P$13") (pintype "bidirectional"))
    )
    (net (code "107") (name "TERMINAL_OUT_3") (class "Default")
      (node (ref "DUE_DIGITAL4") (pin "20") (pinfunction "20_20") (pintype "passive"))
      (node (ref "SPRINGTERMINAL") (pin "P$14") (pinfunction "P$4_P$14") (pintype "bidirectional"))
    )
    (net (code "108") (name "TERMINAL_OUT_4") (class "Default")
      (node (ref "DUE_DIGITAL4") (pin "18") (pinfunction "18_18") (pintype "passive"))
      (node (ref "SPRINGTERMINAL") (pin "P$15") (pinfunction "P$5_P$15") (pintype "bidirectional"))
    )
    (net (code "109") (name "VALVE_SHIFT_RCK") (class "Default")
      (node (ref "DUE_DIGITAL4") (pin "3") (pinfunction "3_3") (pintype "passive"))
      (node (ref "VALVE_REGISTER") (pin "7") (pinfunction "7_7") (pintype "passive"))
    )
    (net (code "110") (name "VCC") (class "Default")
      (node (ref "5V_3V3_1") (pin "1") (pinfunction "1_1") (pintype "passive"))
      (node (ref "5V_3V3_2") (pin "1") (pinfunction "1_1") (pintype "passive"))
      (node (ref "5V_3V3_3") (pin "1") (pinfunction "1_1") (pintype "passive"))
      (node (ref "C1") (pin "1") (pinfunction "1_1") (pintype "passive"))
      (node (ref "C2") (pin "1") (pinfunction "1_1") (pintype "passive"))
      (node (ref "C3") (pin "1") (pinfunction "1_1") (pintype "passive"))
      (node (ref "C6") (pin "1") (pinfunction "1_1") (pintype "passive"))
      (node (ref "DUE_PWR") (pin "2") (pinfunction "2_2") (pintype "passive"))
      (node (ref "OPTOCOUPLER") (pin "8") (pinfunction "8_8") (pintype "passive"))
      (node (ref "PORT1") (pin "2") (pinfunction "2_2") (pintype "bidirectional"))
      (node (ref "PORT2") (pin "2") (pinfunction "2_2") (pintype "bidirectional"))
      (node (ref "PORT3") (pin "2") (pinfunction "2_2") (pintype "bidirectional"))
      (node (ref "PORT4") (pin "2") (pinfunction "2_2") (pintype "bidirectional"))
      (node (ref "PORT5") (pin "2") (pinfunction "2_2") (pintype "bidirectional"))
      (node (ref "PORT6") (pin "2") (pinfunction "2_2") (pintype "bidirectional"))
      (node (ref "PORT7") (pin "2") (pinfunction "2_2") (pintype "bidirectional"))
      (node (ref "PORT8") (pin "2") (pinfunction "2_2") (pintype "bidirectional"))
      (node (ref "Q3") (pin "G") (pinfunction "G_G") (pintype "passive"))
      (node (ref "Q4") (pin "G") (pinfunction "G_G") (pintype "passive"))
    )
    (net (code "111") (name "VIN") (class "Default")
      (node (ref "DUE_PWR") (pin "6") (pinfunction "6_6") (pintype "passive"))
    )
    (net (code "112") (name "unconnected-(5V_3V3_1-Pad11)") (class "Default")
      (node (ref "5V_3V3_1") (pin "11") (pinfunction "11_11") (pintype "passive"))
    )
    (net (code "113") (name "unconnected-(5V_3V3_1-Pad12)") (class "Default")
      (node (ref "5V_3V3_1") (pin "12") (pinfunction "12_12") (pintype "passive"))
    )
    (net (code "114") (name "unconnected-(5V_3V3_1-Pad13)") (class "Default")
      (node (ref "5V_3V3_1") (pin "13") (pinfunction "13_13") (pintype "passive"))
    )
    (net (code "115") (name "unconnected-(5V_3V3_1-Pad14)") (class "Default")
      (node (ref "5V_3V3_1") (pin "14") (pinfunction "14_14") (pintype "passive"))
    )
    (net (code "116") (name "unconnected-(5V_3V3_1-Pad15)") (class "Default")
      (node (ref "5V_3V3_1") (pin "15") (pinfunction "15_15") (pintype "passive"))
    )
    (net (code "117") (name "unconnected-(5V_3V3_1-Pad16)") (class "Default")
      (node (ref "5V_3V3_1") (pin "16") (pinfunction "16_16") (pintype "passive"))
    )
    (net (code "118") (name "unconnected-(5V_3V3_2-Pad13)") (class "Default")
      (node (ref "5V_3V3_2") (pin "13") (pinfunction "13_13") (pintype "passive"))
    )
    (net (code "119") (name "unconnected-(5V_3V3_2-Pad16)") (class "Default")
      (node (ref "5V_3V3_2") (pin "16") (pinfunction "16_16") (pintype "passive"))
    )
    (net (code "120") (name "unconnected-(5V_3V3_3-Pad11)") (class "Default")
      (node (ref "5V_3V3_3") (pin "11") (pinfunction "11_11") (pintype "passive"))
    )
    (net (code "121") (name "unconnected-(5V_3V3_3-Pad12)") (class "Default")
      (node (ref "5V_3V3_3") (pin "12") (pinfunction "12_12") (pintype "passive"))
    )
    (net (code "122") (name "unconnected-(5V_3V3_3-Pad13)") (class "Default")
      (node (ref "5V_3V3_3") (pin "13") (pinfunction "13_13") (pintype "passive"))
    )
    (net (code "123") (name "unconnected-(5V_3V3_3-Pad14)") (class "Default")
      (node (ref "5V_3V3_3") (pin "14") (pinfunction "14_14") (pintype "passive"))
    )
    (net (code "124") (name "unconnected-(5V_3V3_3-Pad15)") (class "Default")
      (node (ref "5V_3V3_3") (pin "15") (pinfunction "15_15") (pintype "passive"))
    )
    (net (code "125") (name "unconnected-(5V_3V3_3-Pad16)") (class "Default")
      (node (ref "5V_3V3_3") (pin "16") (pinfunction "16_16") (pintype "passive"))
    )
    (net (code "126") (name "unconnected-(ICSP-Pad1)") (class "Default")
      (node (ref "ICSP") (pin "1") (pinfunction "1_1") (pintype "passive"))
    )
    (net (code "127") (name "unconnected-(ICSP-Pad2)") (class "Default")
      (node (ref "ICSP") (pin "2") (pinfunction "2_2") (pintype "passive"))
    )
    (net (code "128") (name "unconnected-(ICSP-Pad5)") (class "Default")
      (node (ref "ICSP") (pin "5") (pinfunction "5_5") (pintype "passive"))
    )
    (net (code "129") (name "unconnected-(SERIAL1-Pad6)") (class "Default")
      (node (ref "SERIAL1") (pin "6") (pinfunction "6_6") (pintype "bidirectional"))
    )
    (net (code "130") (name "unconnected-(SERIAL1-Pad7)") (class "Default")
      (node (ref "SERIAL1") (pin "7") (pinfunction "7_7") (pintype "bidirectional"))
    )
    (net (code "131") (name "unconnected-(SERIAL1-Pad8)") (class "Default")
      (node (ref "SERIAL1") (pin "8") (pinfunction "8_8") (pintype "bidirectional"))
    )
    (net (code "132") (name "unconnected-(SERIAL2-Pad6)") (class "Default")
      (node (ref "SERIAL2") (pin "6") (pinfunction "6_6") (pintype "bidirectional"))
    )
    (net (code "133") (name "unconnected-(SERIAL2-Pad7)") (class "Default")
      (node (ref "SERIAL2") (pin "7") (pinfunction "7_7") (pintype "bidirectional"))
    )
    (net (code "134") (name "unconnected-(SERIAL2-Pad8)") (class "Default")
      (node (ref "SERIAL2") (pin "8") (pinfunction "8_8") (pintype "bidirectional"))
    )
    (net (code "135") (name "unconnected-(VALVE_REGISTER-Pad13)") (class "Default")
      (node (ref "VALVE_REGISTER") (pin "13") (pinfunction "13_13") (pintype "passive"))
    )
  )
)
